# RDA5807FP_SETUP.net
KiCad netlist of a schematic drawn in EAGLE
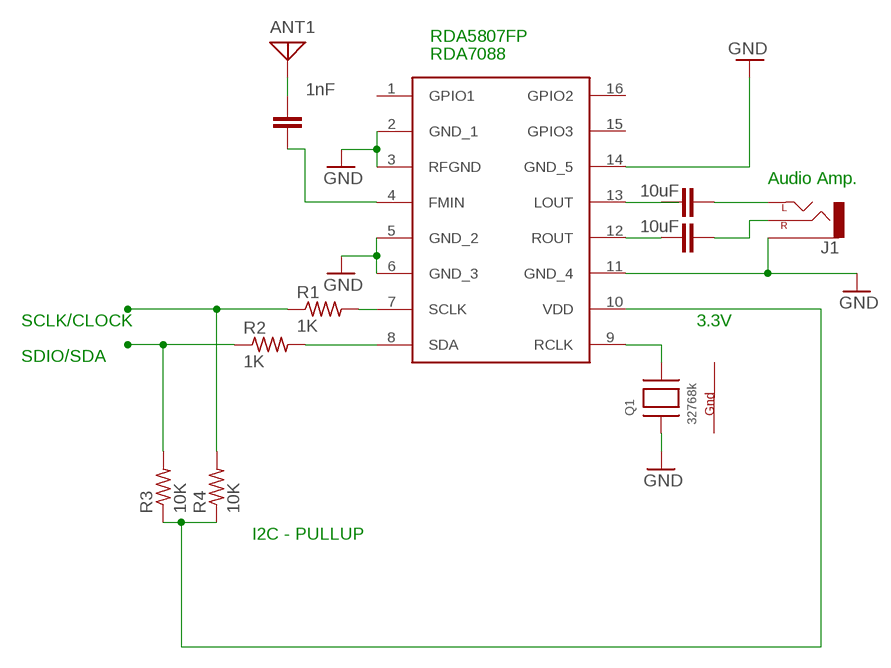
[diagram p0: schematic, sheet 1]

(export (version "E")
  (design (tool "Eeschema 10.0.6"))
  (components
    (comp (ref "ANT1")
      (value "ANTENNA")
      (footprint "eagle-import:PAD-01")
      (libsource (lib "eagle-import") (part "ANTENNA"))
    )
    (comp (ref "J1")
      (value "AUDIO_JACK_2.5MMSPECIAL_POGO_PINS")
      (footprint "eagle-import:STEREOJACK2.5MM_SPECIAL_POGOPINS")
      (libsource (lib "eagle-import") (part "AUDIO_JACK_2.5MMSPECIAL_POGO_PINS"))
    )
    (comp (ref "Q1")
      (value "32768k")
      (footprint "eagle-import:NX3225")
      (libsource (lib "eagle-import") (part "XTAL-4-3225"))
    )
    (comp (ref "R1")
      (value "1K")
      (footprint "eagle-import:0204V")
      (libsource (lib "eagle-import") (part "R-US_0204/2V"))
    )
    (comp (ref "R2")
      (value "1K")
      (footprint "eagle-import:0204V")
      (libsource (lib "eagle-import") (part "R-US_0204/2V"))
    )
    (comp (ref "R3")
      (value "10K")
      (footprint "eagle-import:0204V")
      (libsource (lib "eagle-import") (part "R-US_0204/2V"))
    )
    (comp (ref "R4")
      (value "10K")
      (footprint "eagle-import:0204V")
      (libsource (lib "eagle-import") (part "R-US_0204/2V"))
    )
    (comp (ref "U$1")
      (value "RDA5807FPRDA5807FP")
      (footprint "eagle-import:RDA5807FP")
      (libsource (lib "eagle-import") (part "RDA5807FPRDA5807FP"))
    )
  )
  (nets
    (net (code "1") (name "/G1") (class "Default")
      (node (ref "Q1") (pin "4") (pinfunction "G1_4") (pintype "power_in"))
    )
    (net (code "2") (name "/G2") (class "Default")
      (node (ref "Q1") (pin "2") (pinfunction "G2_2") (pintype "power_in"))
    )
    (net (code "3") (name "GND") (class "Default")
      (node (ref "J1") (pin "RING1") (pinfunction "SLEEVE_RING1") (pintype "bidirectional"))
      (node (ref "Q1") (pin "1") (pinfunction "X1_1") (pintype "bidirectional"))
      (node (ref "U$1") (pin "11") (pinfunction "GND_4_11") (pintype "bidirectional"))
      (node (ref "U$1") (pin "14") (pinfunction "GND_5_14") (pintype "bidirectional"))
      (node (ref "U$1") (pin "2") (pinfunction "GND_1_2") (pintype "bidirectional"))
      (node (ref "U$1") (pin "3") (pinfunction "RFGND_3") (pintype "bidirectional"))
      (node (ref "U$1") (pin "5") (pinfunction "GND_2_5") (pintype "bidirectional"))
      (node (ref "U$1") (pin "6") (pinfunction "GND_3_6") (pintype "bidirectional"))
    )
    (net (code "4") (name "Net-(Q1-X2)") (class "Default")
      (node (ref "Q1") (pin "3") (pinfunction "X2_3") (pintype "bidirectional"))
      (node (ref "U$1") (pin "9") (pinfunction "RCLK_9") (pintype "bidirectional"))
    )
    (net (code "5") (name "Net-(R1-Pad1)") (class "Default")
      (node (ref "R1") (pin "1") (pinfunction "1_1") (pintype "passive"))
      (node (ref "R4") (pin "2") (pinfunction "2_2") (pintype "passive"))
    )
    (net (code "6") (name "Net-(R2-Pad1)") (class "Default")
      (node (ref "R2") (pin "1") (pinfunction "1_1") (pintype "passive"))
      (node (ref "R3") (pin "2") (pinfunction "2_2") (pintype "passive"))
    )
    (net (code "7") (name "Net-(U$1-SCLK)") (class "Default")
      (node (ref "R1") (pin "2") (pinfunction "2_2") (pintype "passive"))
      (node (ref "U$1") (pin "7") (pinfunction "SCLK_7") (pintype "bidirectional"))
    )
    (net (code "8") (name "Net-(U$1-SDA)") (class "Default")
      (node (ref "R2") (pin "2") (pinfunction "2_2") (pintype "passive"))
      (node (ref "U$1") (pin "8") (pinfunction "SDA_8") (pintype "bidirectional"))
    )
    (net (code "9") (name "Net-(U$1-VDD)") (class "Default")
      (node (ref "R3") (pin "1") (pinfunction "1_1") (pintype "passive"))
      (node (ref "R4") (pin "1") (pinfunction "1_1") (pintype "passive"))
      (node (ref "U$1") (pin "10") (pinfunction "VDD_10") (pintype "bidirectional"))
    )
    (net (code "10") (name "unconnected-(ANT1-Pad1)") (class "Default")
      (node (ref "ANT1") (pin "1") (pinfunction "1_1") (pintype "output"))
    )
    (net (code "11") (name "unconnected-(J1-LEFT-PadSHIELD)") (class "Default")
      (node (ref "J1") (pin "SHIELD") (pinfunction "LEFT_SHIELD") (pintype "bidirectional"))
    )
    (net (code "12") (name "unconnected-(J1-RIGHT-PadTIP)") (class "Default")
      (node (ref "J1") (pin "TIP") (pinfunction "RIGHT_TIP") (pintype "bidirectional"))
    )
    (net (code "13") (name "unconnected-(U$1-FMIN-Pad4)") (class "Default")
      (node (ref "U$1") (pin "4") (pinfunction "FMIN_4") (pintype "bidirectional"))
    )
    (net (code "14") (name "unconnected-(U$1-GPIO1-Pad1)") (class "Default")
      (node (ref "U$1") (pin "1") (pinfunction "GPIO1_1") (pintype "bidirectional"))
    )
    (net (code "15") (name "unconnected-(U$1-GPIO2-Pad16)") (class "Default")
      (node (ref "U$1") (pin "16") (pinfunction "GPIO2_16") (pintype "bidirectional"))
    )
    (net (code "16") (name "unconnected-(U$1-GPIO3-Pad15)") (class "Default")
      (node (ref "U$1") (pin "15") (pinfunction "GPIO3_15") (pintype "bidirectional"))
    )
    (net (code "17") (name "unconnected-(U$1-LOUT-Pad13)") (class "Default")
      (node (ref "U$1") (pin "13") (pinfunction "LOUT_13") (pintype "bidirectional"))
    )
    (net (code "18") (name "unconnected-(U$1-ROUT-Pad12)") (class "Default")
      (node (ref "U$1") (pin "12") (pinfunction "ROUT_12") (pintype "bidirectional"))
    )
  )
)
